# test_Project_2026-04-05_21-01-09.net
KiCad netlist of a schematic drawn in EasyEDA Pro
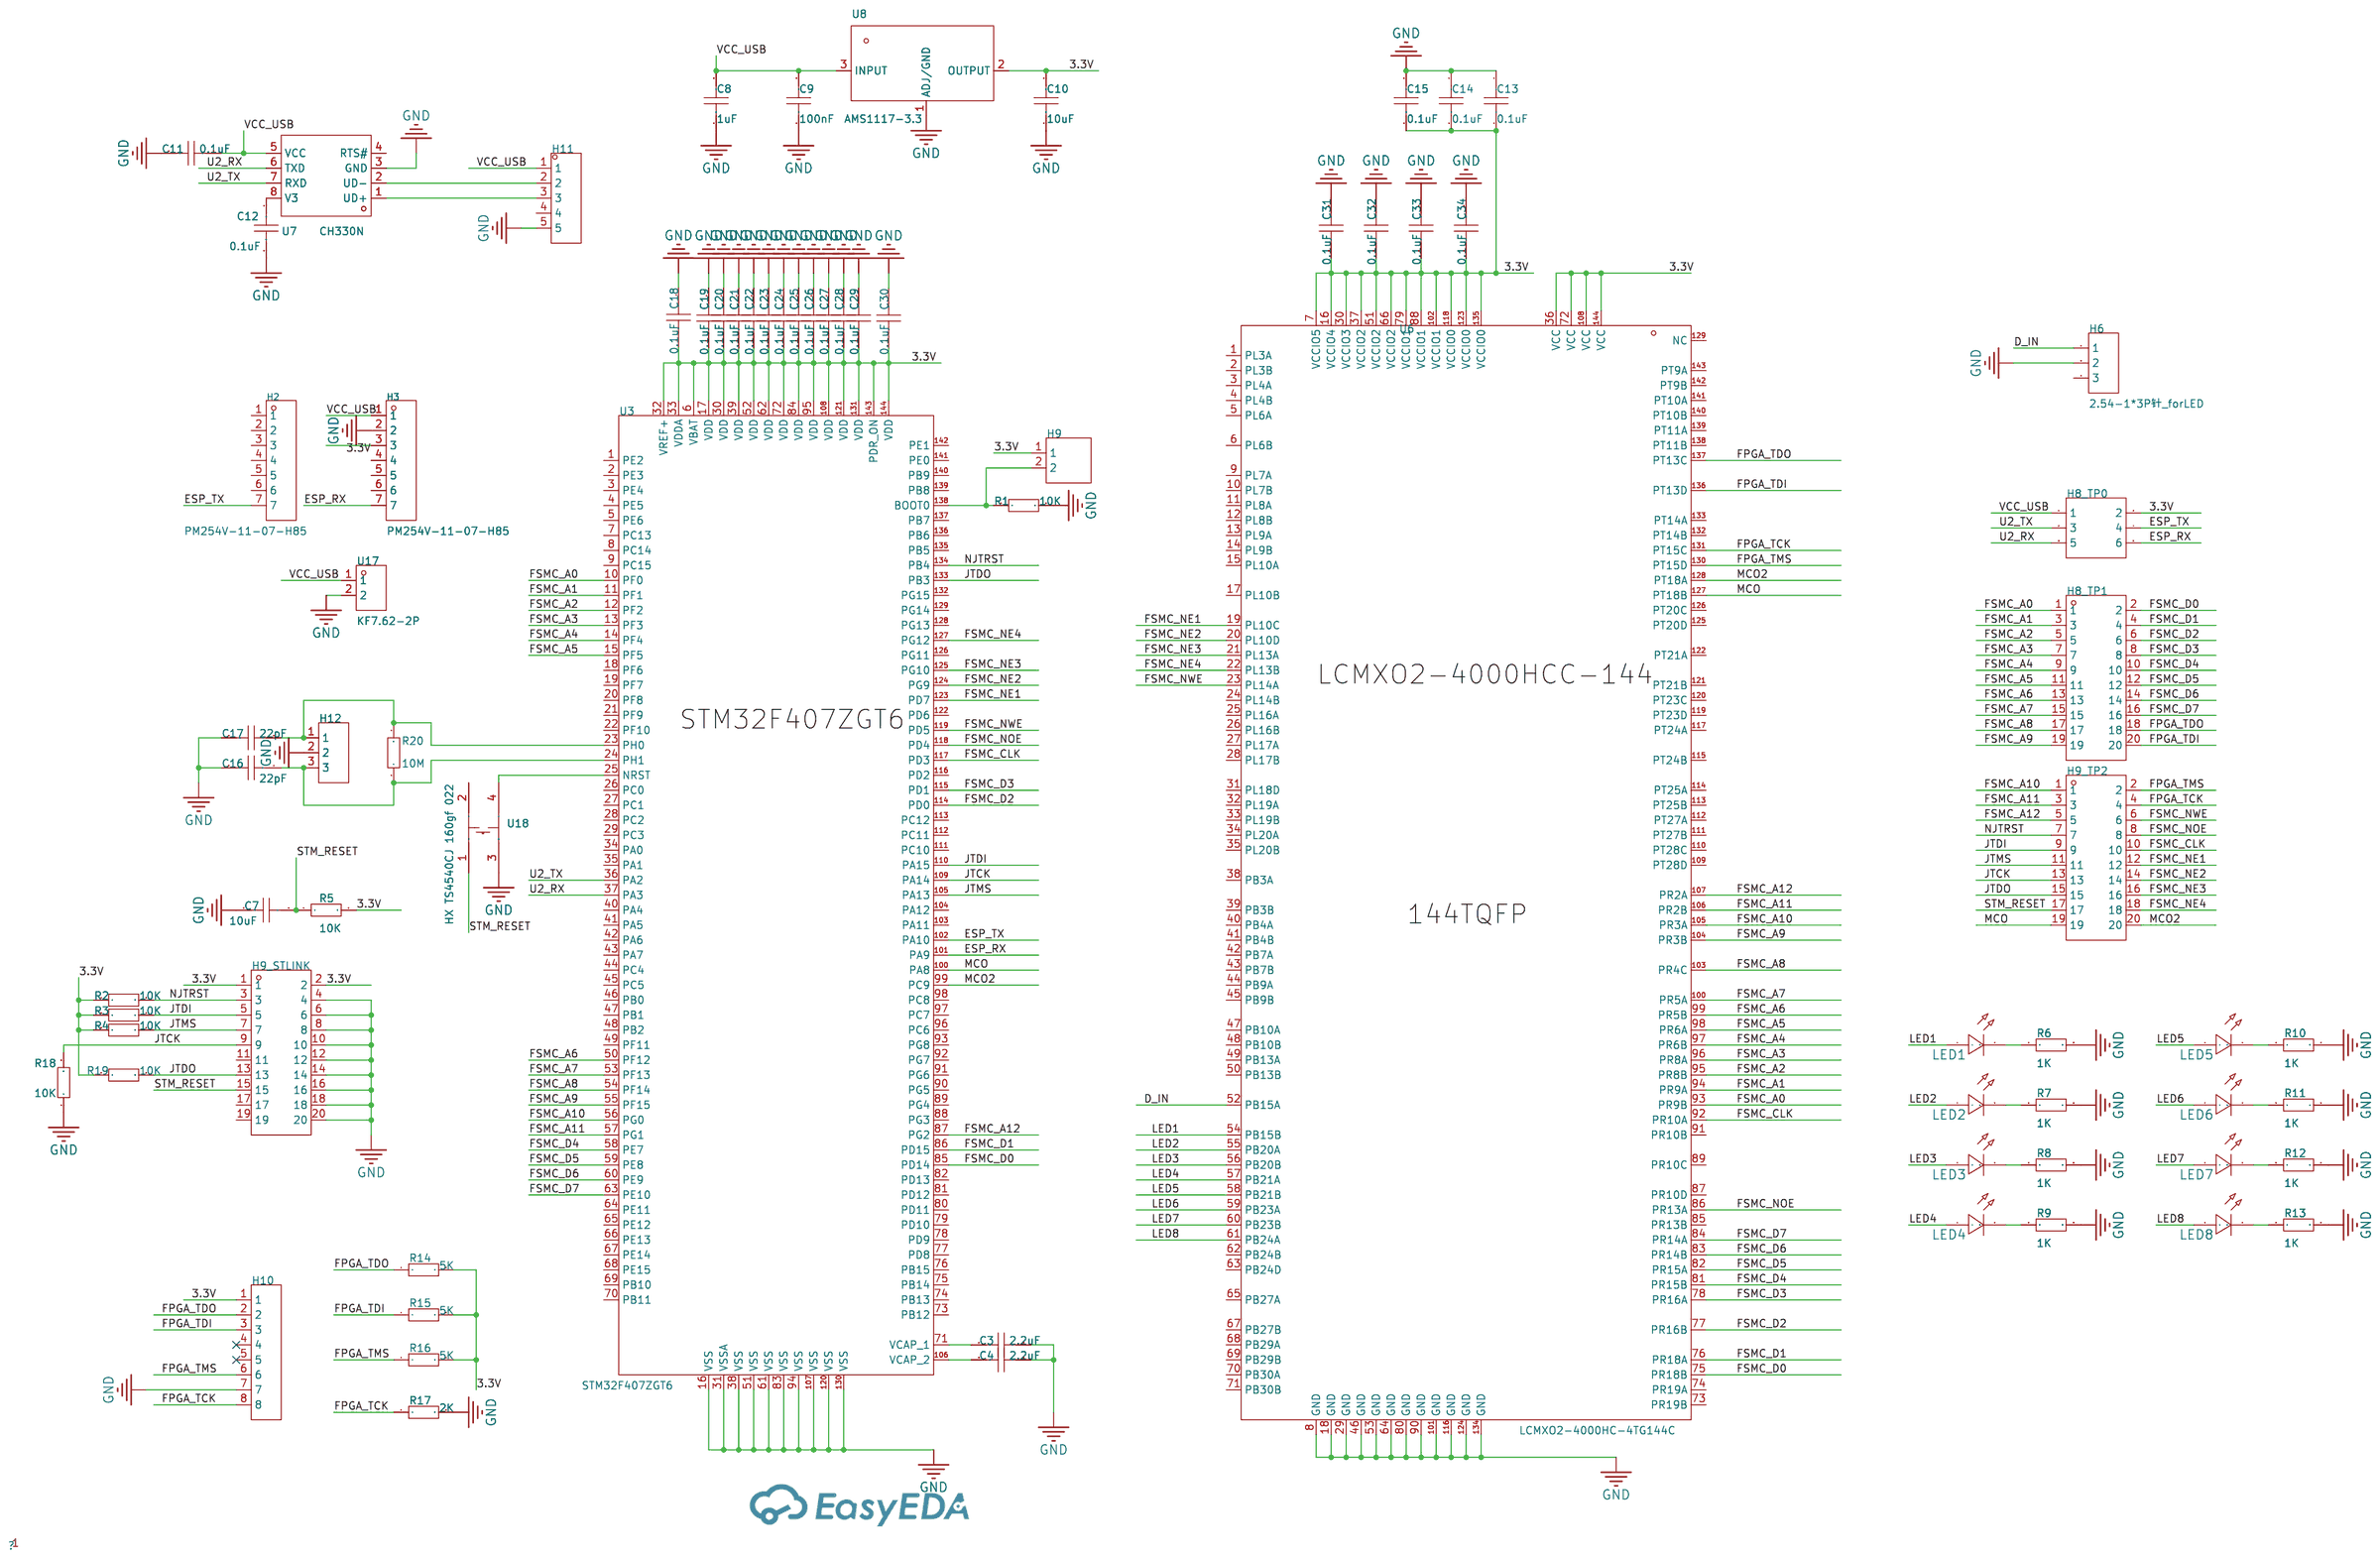
[diagram p0: schematic sheet]

(export (version "E")
  (design (tool "Eeschema 10.0.6"))
  (components
    (comp (ref "C3")
      (value "2.2uF")
      (footprint "easyedapro:C0201")
      (libsource (lib "easyedapro") (part "CAP"))
    )
    (comp (ref "C4")
      (value "2.2uF")
      (footprint "easyedapro:C0201")
      (libsource (lib "easyedapro") (part "CAP"))
    )
    (comp (ref "C7")
      (value "10uF")
      (footprint "easyedapro:C0201")
      (libsource (lib "easyedapro") (part "CAP"))
    )
    (comp (ref "C8") (value "1uF") (footprint "easyedapro:C0201") (libsource (lib "easyedapro") (part "CAP")))
    (comp (ref "C9")
      (value "100nF")
      (footprint "easyedapro:C0201")
      (libsource (lib "easyedapro") (part "CAP"))
    )
    (comp (ref "C10")
      (value "10uF")
      (footprint "easyedapro:C0201")
      (libsource (lib "easyedapro") (part "CAP"))
    )
    (comp (ref "C11")
      (value "0.1uF")
      (footprint "easyedapro:C0201")
      (libsource (lib "easyedapro") (part "CAP"))
    )
    (comp (ref "C12")
      (value "0.1uF")
      (footprint "easyedapro:C0201")
      (libsource (lib "easyedapro") (part "CAP"))
    )
    (comp (ref "C13")
      (value "0.1uF")
      (footprint "easyedapro:C0201")
      (libsource (lib "easyedapro") (part "CAP"))
    )
    (comp (ref "C14")
      (value "0.1uF")
      (footprint "easyedapro:C0201")
      (libsource (lib "easyedapro") (part "CAP"))
    )
    (comp (ref "C15")
      (value "0.1uF")
      (footprint "easyedapro:C0201")
      (libsource (lib "easyedapro") (part "CAP"))
    )
    (comp (ref "C16")
      (value "22pF")
      (footprint "easyedapro:C0201")
      (libsource (lib "easyedapro") (part "CAP"))
    )
    (comp (ref "C17")
      (value "22pF")
      (footprint "easyedapro:C0201")
      (libsource (lib "easyedapro") (part "CAP"))
    )
    (comp (ref "C18")
      (value "0.1uF")
      (footprint "easyedapro:C0201")
      (libsource (lib "easyedapro") (part "CAP"))
    )
    (comp (ref "C19")
      (value "0.1uF")
      (footprint "easyedapro:C0201")
      (libsource (lib "easyedapro") (part "CAP"))
    )
    (comp (ref "C20")
      (value "0.1uF")
      (footprint "easyedapro:C0201")
      (libsource (lib "easyedapro") (part "CAP"))
    )
    (comp (ref "C21")
      (value "0.1uF")
      (footprint "easyedapro:C0201")
      (libsource (lib "easyedapro") (part "CAP"))
    )
    (comp (ref "C22")
      (value "0.1uF")
      (footprint "easyedapro:C0201")
      (libsource (lib "easyedapro") (part "CAP"))
    )
    (comp (ref "C23")
      (value "0.1uF")
      (footprint "easyedapro:C0201")
      (libsource (lib "easyedapro") (part "CAP"))
    )
    (comp (ref "C24")
      (value "0.1uF")
      (footprint "easyedapro:C0201")
      (libsource (lib "easyedapro") (part "CAP"))
    )
    (comp (ref "C25")
      (value "0.1uF")
      (footprint "easyedapro:C0201")
      (libsource (lib "easyedapro") (part "CAP"))
    )
    (comp (ref "C26")
      (value "0.1uF")
      (footprint "easyedapro:C0201")
      (libsource (lib "easyedapro") (part "CAP"))
    )
    (comp (ref "C27")
      (value "0.1uF")
      (footprint "easyedapro:C0201")
      (libsource (lib "easyedapro") (part "CAP"))
    )
    (comp (ref "C28")
      (value "0.1uF")
      (footprint "easyedapro:C0201")
      (libsource (lib "easyedapro") (part "CAP"))
    )
    (comp (ref "C29")
      (value "0.1uF")
      (footprint "easyedapro:C0201")
      (libsource (lib "easyedapro") (part "CAP"))
    )
    (comp (ref "C30")
      (value "0.1uF")
      (footprint "easyedapro:C0201")
      (libsource (lib "easyedapro") (part "CAP"))
    )
    (comp (ref "C31")
      (value "0.1uF")
      (footprint "easyedapro:C0201")
      (libsource (lib "easyedapro") (part "CAP"))
    )
    (comp (ref "C32")
      (value "0.1uF")
      (footprint "easyedapro:C0201")
      (libsource (lib "easyedapro") (part "CAP"))
    )
    (comp (ref "C33")
      (value "0.1uF")
      (footprint "easyedapro:C0201")
      (libsource (lib "easyedapro") (part "CAP"))
    )
    (comp (ref "C34")
      (value "0.1uF")
      (footprint "easyedapro:C0201")
      (libsource (lib "easyedapro") (part "CAP"))
    )
    (comp (ref "H2")
      (value "PM254V-11-07-H85")
      (footprint "easyedapro:HDR-TH_7P-P2.54-V-F")
      (fields (field (name "Manufacturer") "XFCN(兴飞)"))
      (libsource (lib "easyedapro") (part "PM254V-11-07-H85"))
    )
    (comp (ref "H3")
      (value "PM254V-11-07-H85")
      (footprint "easyedapro:HDR-TH_7P-P2.54-V-F")
      (fields (field (name "Manufacturer") "XFCN(兴飞)"))
      (libsource (lib "easyedapro") (part "PM254V-11-07-H85"))
    )
    (comp (ref "H6")
      (value "2.54-1*3P针_forLED")
      (footprint "easyedapro:HDR-TH_3P-P2.54-V-M-1")
      (fields (field (name "Manufacturer") "BOOMELE(博穆精密)"))
      (libsource (lib "easyedapro") (part "Header-Male-2.54_1x3"))
    )
    (comp (ref "H8_TP0")
      (value "~")
      (footprint "easyedapro:HDR-TH_6P-P2.54-V-R2-C3-S2.54_A2541WV-2X3P")
      (libsource (lib "easyedapro") (part "HDR-M-2.54_2x3"))
    )
    (comp (ref "H8_TP1")
      (value "~")
      (footprint "easyedapro:HDR-TH_20P-P2.54-V-M-R2-C10-S2.54")
      (libsource (lib "easyedapro") (part "HDR-M-2.54_2x10"))
    )
    (comp (ref "H9")
      (value "~")
      (footprint "easyedapro:HDR-TH_2P-P2.54-V-M-1")
      (libsource (lib "easyedapro") (part "210S-1*2P L=11.6MMGold-plated black"))
    )
    (comp (ref "H9_STLINK")
      (value "~")
      (footprint "easyedapro:HDR-TH_20P-P2.54-V-M-R2-C10-S2.54")
      (libsource (lib "easyedapro") (part "HDR-M-2.54_2x10"))
    )
    (comp (ref "H9_TP2")
      (value "~")
      (footprint "easyedapro:HDR-TH_20P-P2.54-V-M-R2-C10-S2.54")
      (libsource (lib "easyedapro") (part "HDR-M-2.54_2x10"))
    )
    (comp (ref "H10")
      (value "~")
      (footprint "easyedapro:HDR-TH_8P-P2.54-V-F-1")
      (libsource (lib "easyedapro") (part "Header-Female-2.54_1x8"))
    )
    (comp (ref "H11")
      (value "~")
      (footprint "easyedapro:HDR-TH_5P-P2.54-V-M")
      (libsource (lib "easyedapro") (part "MTP125-1105S1"))
    )
    (comp (ref "H12")
      (value "~")
      (footprint "easyedapro:HDR-TH_3P-P2.54-V-F")
      (libsource (lib "easyedapro") (part "PM254V-11-03-H85"))
    )
    (comp (ref "LED1")
      (value "~")
      (footprint "easyedapro:LED0805-R-RD")
      (libsource (lib "easyedapro") (part "LED_R"))
    )
    (comp (ref "LED2")
      (value "~")
      (footprint "easyedapro:LED0805-R-RD")
      (libsource (lib "easyedapro") (part "LED_R"))
    )
    (comp (ref "LED3")
      (value "~")
      (footprint "easyedapro:LED0805-R-RD")
      (libsource (lib "easyedapro") (part "LED_R"))
    )
    (comp (ref "LED4")
      (value "~")
      (footprint "easyedapro:LED0805-R-RD")
      (libsource (lib "easyedapro") (part "LED_R"))
    )
    (comp (ref "LED5")
      (value "~")
      (footprint "easyedapro:LED0805-R-RD")
      (libsource (lib "easyedapro") (part "LED_R"))
    )
    (comp (ref "LED6")
      (value "~")
      (footprint "easyedapro:LED0805-R-RD")
      (libsource (lib "easyedapro") (part "LED_R"))
    )
    (comp (ref "LED7")
      (value "~")
      (footprint "easyedapro:LED0805-R-RD")
      (libsource (lib "easyedapro") (part "LED_R"))
    )
    (comp (ref "LED8")
      (value "~")
      (footprint "easyedapro:LED0805-R-RD")
      (libsource (lib "easyedapro") (part "LED_R"))
    )
    (comp (ref "R1") (value "10K") (footprint "easyedapro:R0805") (libsource (lib "easyedapro") (part "Res")))
    (comp (ref "R2") (value "10K") (footprint "easyedapro:R0805") (libsource (lib "easyedapro") (part "Res")))
    (comp (ref "R3") (value "10K") (footprint "easyedapro:R0805") (libsource (lib "easyedapro") (part "Res")))
    (comp (ref "R4") (value "10K") (footprint "easyedapro:R0805") (libsource (lib "easyedapro") (part "Res")))
    (comp (ref "R5") (value "10K") (footprint "easyedapro:R0805") (libsource (lib "easyedapro") (part "Res")))
    (comp (ref "R6") (value "1K") (footprint "easyedapro:R0805") (libsource (lib "easyedapro") (part "Res")))
    (comp (ref "R7") (value "1K") (footprint "easyedapro:R0805") (libsource (lib "easyedapro") (part "Res")))
    (comp (ref "R8") (value "1K") (footprint "easyedapro:R0805") (libsource (lib "easyedapro") (part "Res")))
    (comp (ref "R9") (value "1K") (footprint "easyedapro:R0805") (libsource (lib "easyedapro") (part "Res")))
    (comp (ref "R10") (value "1K") (footprint "easyedapro:R0805") (libsource (lib "easyedapro") (part "Res")))
    (comp (ref "R11") (value "1K") (footprint "easyedapro:R0805") (libsource (lib "easyedapro") (part "Res")))
    (comp (ref "R12") (value "1K") (footprint "easyedapro:R0805") (libsource (lib "easyedapro") (part "Res")))
    (comp (ref "R13") (value "1K") (footprint "easyedapro:R0805") (libsource (lib "easyedapro") (part "Res")))
    (comp (ref "R14") (value "5K") (footprint "easyedapro:R0805") (libsource (lib "easyedapro") (part "Res")))
    (comp (ref "R15") (value "5K") (footprint "easyedapro:R0805") (libsource (lib "easyedapro") (part "Res")))
    (comp (ref "R16") (value "5K") (footprint "easyedapro:R0805") (libsource (lib "easyedapro") (part "Res")))
    (comp (ref "R17") (value "2K") (footprint "easyedapro:R0805") (libsource (lib "easyedapro") (part "Res")))
    (comp (ref "R18")
      (value "10K")
      (footprint "easyedapro:R0805")
      (libsource (lib "easyedapro") (part "Res"))
    )
    (comp (ref "R19")
      (value "10K")
      (footprint "easyedapro:R0805")
      (libsource (lib "easyedapro") (part "Res"))
    )
    (comp (ref "R20")
      (value "10M")
      (footprint "easyedapro:R0805")
      (libsource (lib "easyedapro") (part "Res"))
    )
    (comp (ref "U3")
      (value "STM32F407ZGT6")
      (footprint "easyedapro:LQFP-144_L20.0-W20.0-P0.50-LS22.0-BL")
      (fields (field (name "Manufacturer") "ST(意法半导体)"))
      (libsource (lib "easyedapro") (part "STM32F407ZGT6"))
    )
    (comp (ref "U6")
      (value "LCMXO2-4000HC-4TG144C")
      (footprint "easyedapro:TQFP-144_L20.0-W20.0-P0.50-LS22.0-BL")
      (fields (field (name "Manufacturer") "LATTICE(莱迪思)"))
      (libsource (lib "easyedapro") (part "LCMXO2-4000HC-4TG144C"))
    )
    (comp (ref "U7")
      (value "CH330N")
      (footprint "easyedapro:SOP-8_L4.9-W3.9-P1.27-LS6.0-BL")
      (fields (field (name "Manufacturer") "WCH(南京沁恒)"))
      (libsource (lib "easyedapro") (part "CH330N"))
    )
    (comp (ref "U8")
      (value "AMS1117-3.3")
      (footprint "easyedapro:TO-252-2_L6.6-W5.6-P2.3-LS9.7")
      (fields (field (name "Manufacturer") "YONGYUTAI(永裕泰)"))
      (libsource (lib "easyedapro") (part "AMS1117-3.3_C41414107"))
    )
    (comp (ref "U17")
      (value "KF7.62-2P")
      (footprint "easyedapro:CONN-TH_KF7.62-2P")
      (fields (field (name "Manufacturer") "KEFA(科发)"))
      (libsource (lib "easyedapro") (part "KF7.62-2P"))
    )
    (comp (ref "U18")
      (value "HX TS4540CJ 160gf 022")
      (footprint "easyedapro:KEY-TH_4P-L4.5-W4.5-P3.00-LS5.0-TL")
      (fields (field (name "Manufacturer") "hanxia(韩下)"))
      (libsource (lib "easyedapro") (part "HX TS4540CJ 160GF 022"))
    )
  )
  (nets
    (net (code "1") (name "/3.3V") (class "Default")
      (node (ref "C10") (pin "1") (pinfunction "1_1") (pintype "input"))
      (node (ref "C13") (pin "2") (pinfunction "2_2") (pintype "input"))
      (node (ref "C14") (pin "2") (pinfunction "2_2") (pintype "input"))
      (node (ref "C15") (pin "2") (pinfunction "2_2") (pintype "input"))
      (node (ref "C18") (pin "2") (pinfunction "2_2") (pintype "input"))
      (node (ref "C19") (pin "2") (pinfunction "2_2") (pintype "input"))
      (node (ref "C20") (pin "2") (pinfunction "2_2") (pintype "input"))
      (node (ref "C21") (pin "2") (pinfunction "2_2") (pintype "input"))
      (node (ref "C22") (pin "2") (pinfunction "2_2") (pintype "input"))
      (node (ref "C23") (pin "2") (pinfunction "2_2") (pintype "input"))
      (node (ref "C24") (pin "2") (pinfunction "2_2") (pintype "input"))
      (node (ref "C25") (pin "2") (pinfunction "2_2") (pintype "input"))
      (node (ref "C26") (pin "2") (pinfunction "2_2") (pintype "input"))
      (node (ref "C27") (pin "2") (pinfunction "2_2") (pintype "input"))
      (node (ref "C28") (pin "2") (pinfunction "2_2") (pintype "input"))
      (node (ref "C29") (pin "2") (pinfunction "2_2") (pintype "input"))
      (node (ref "C30") (pin "2") (pinfunction "2_2") (pintype "input"))
      (node (ref "C31") (pin "2") (pinfunction "2_2") (pintype "input"))
      (node (ref "C32") (pin "2") (pinfunction "2_2") (pintype "input"))
      (node (ref "C33") (pin "2") (pinfunction "2_2") (pintype "input"))
      (node (ref "C34") (pin "2") (pinfunction "2_2") (pintype "input"))
      (node (ref "H10") (pin "1") (pinfunction "1_1") (pintype "unspecified"))
      (node (ref "H3") (pin "3") (pinfunction "3_3") (pintype "input"))
      (node (ref "H8_TP0") (pin "2") (pinfunction "2_2") (pintype "input"))
      (node (ref "H9") (pin "1") (pinfunction "1_1") (pintype "unspecified"))
      (node (ref "H9_STLINK") (pin "1") (pinfunction "1_1") (pintype "input"))
      (node (ref "H9_STLINK") (pin "2") (pinfunction "2_2") (pintype "input"))
      (node (ref "R14") (pin "2") (pinfunction "2_2") (pintype "input"))
      (node (ref "R15") (pin "2") (pinfunction "2_2") (pintype "input"))
      (node (ref "R16") (pin "2") (pinfunction "2_2") (pintype "input"))
      (node (ref "R19") (pin "1") (pinfunction "1_1") (pintype "input"))
      (node (ref "R2") (pin "1") (pinfunction "1_1") (pintype "input"))
      (node (ref "R3") (pin "1") (pinfunction "1_1") (pintype "input"))
      (node (ref "R4") (pin "1") (pinfunction "1_1") (pintype "input"))
      (node (ref "R5") (pin "2") (pinfunction "2_2") (pintype "input"))
      (node (ref "U3") (pin "108") (pinfunction "VDD_108") (pintype "unspecified"))
      (node (ref "U3") (pin "121") (pinfunction "VDD_121") (pintype "unspecified"))
      (node (ref "U3") (pin "131") (pinfunction "VDD_131") (pintype "unspecified"))
      (node (ref "U3") (pin "143") (pinfunction "PDR_ON_143") (pintype "unspecified"))
      (node (ref "U3") (pin "144") (pinfunction "VDD_144") (pintype "unspecified"))
      (node (ref "U3") (pin "17") (pinfunction "VDD_17") (pintype "unspecified"))
      (node (ref "U3") (pin "30") (pinfunction "VDD_30") (pintype "unspecified"))
      (node (ref "U3") (pin "32") (pinfunction "VREF+_32") (pintype "unspecified"))
      (node (ref "U3") (pin "33") (pinfunction "VDDA_33") (pintype "unspecified"))
      (node (ref "U3") (pin "39") (pinfunction "VDD_39") (pintype "unspecified"))
      (node (ref "U3") (pin "52") (pinfunction "VDD_52") (pintype "unspecified"))
      (node (ref "U3") (pin "6") (pinfunction "VBAT_6") (pintype "unspecified"))
      (node (ref "U3") (pin "62") (pinfunction "VDD_62") (pintype "unspecified"))
      (node (ref "U3") (pin "72") (pinfunction "VDD_72") (pintype "unspecified"))
      (node (ref "U3") (pin "84") (pinfunction "VDD_84") (pintype "unspecified"))
      (node (ref "U3") (pin "95") (pinfunction "VDD_95") (pintype "unspecified"))
      (node (ref "U6") (pin "102") (pinfunction "VCCIO1_102") (pintype "unspecified"))
      (node (ref "U6") (pin "108") (pinfunction "VCC_108") (pintype "unspecified"))
      (node (ref "U6") (pin "118") (pinfunction "VCCIO0_118") (pintype "unspecified"))
      (node (ref "U6") (pin "123") (pinfunction "VCCIO0_123") (pintype "unspecified"))
      (node (ref "U6") (pin "135") (pinfunction "VCCIO0_135") (pintype "unspecified"))
      (node (ref "U6") (pin "144") (pinfunction "VCC_144") (pintype "unspecified"))
      (node (ref "U6") (pin "16") (pinfunction "VCCIO4_16") (pintype "unspecified"))
      (node (ref "U6") (pin "30") (pinfunction "VCCIO3_30") (pintype "unspecified"))
      (node (ref "U6") (pin "36") (pinfunction "VCC_36") (pintype "unspecified"))
      (node (ref "U6") (pin "37") (pinfunction "VCCIO2_37") (pintype "unspecified"))
      (node (ref "U6") (pin "51") (pinfunction "VCCIO2_51") (pintype "unspecified"))
      (node (ref "U6") (pin "66") (pinfunction "VCCIO2_66") (pintype "unspecified"))
      (node (ref "U6") (pin "7") (pinfunction "VCCIO5_7") (pintype "unspecified"))
      (node (ref "U6") (pin "72") (pinfunction "VCC_72") (pintype "unspecified"))
      (node (ref "U6") (pin "79") (pinfunction "VCCIO1_79") (pintype "unspecified"))
      (node (ref "U6") (pin "88") (pinfunction "VCCIO1_88") (pintype "unspecified"))
      (node (ref "U8") (pin "2") (pinfunction "OUTPUT_2") (pintype "unspecified"))
    )
    (net (code "2") (name "/D_IN") (class "Default")
      (node (ref "H6") (pin "1") (pinfunction "1_1") (pintype "input"))
      (node (ref "U6") (pin "52") (pinfunction "PB15A_52") (pintype "unspecified"))
    )
    (net (code "3") (name "/ESP_RX") (class "Default")
      (node (ref "H3") (pin "7") (pinfunction "7_7") (pintype "input"))
      (node (ref "H8_TP0") (pin "6") (pinfunction "6_6") (pintype "input"))
      (node (ref "U3") (pin "101") (pinfunction "PA9_101") (pintype "unspecified"))
    )
    (net (code "4") (name "/ESP_TX") (class "Default")
      (node (ref "H2") (pin "7") (pinfunction "7_7") (pintype "input"))
      (node (ref "H8_TP0") (pin "4") (pinfunction "4_4") (pintype "input"))
      (node (ref "U3") (pin "102") (pinfunction "PA10_102") (pintype "unspecified"))
    )
    (net (code "5") (name "/FPGA_TCK") (class "Default")
      (node (ref "H10") (pin "8") (pinfunction "8_8") (pintype "unspecified"))
      (node (ref "H9_TP2") (pin "4") (pinfunction "4_4") (pintype "input"))
      (node (ref "R17") (pin "1") (pinfunction "1_1") (pintype "input"))
      (node (ref "U6") (pin "131") (pinfunction "PT15C_131") (pintype "unspecified"))
    )
    (net (code "6") (name "/FPGA_TDI") (class "Default")
      (node (ref "H10") (pin "3") (pinfunction "3_3") (pintype "unspecified"))
      (node (ref "H8_TP1") (pin "20") (pinfunction "20_20") (pintype "input"))
      (node (ref "R15") (pin "1") (pinfunction "1_1") (pintype "input"))
      (node (ref "U6") (pin "136") (pinfunction "PT13D_136") (pintype "unspecified"))
    )
    (net (code "7") (name "/FPGA_TDO") (class "Default")
      (node (ref "H10") (pin "2") (pinfunction "2_2") (pintype "unspecified"))
      (node (ref "H8_TP1") (pin "18") (pinfunction "18_18") (pintype "input"))
      (node (ref "R14") (pin "1") (pinfunction "1_1") (pintype "input"))
      (node (ref "U6") (pin "137") (pinfunction "PT13C_137") (pintype "unspecified"))
    )
    (net (code "8") (name "/FPGA_TMS") (class "Default")
      (node (ref "H10") (pin "6") (pinfunction "6_6") (pintype "unspecified"))
      (node (ref "H9_TP2") (pin "2") (pinfunction "2_2") (pintype "input"))
      (node (ref "R16") (pin "1") (pinfunction "1_1") (pintype "input"))
      (node (ref "U6") (pin "130") (pinfunction "PT15D_130") (pintype "unspecified"))
    )
    (net (code "9") (name "/FSMC_A0") (class "Default")
      (node (ref "H8_TP1") (pin "1") (pinfunction "1_1") (pintype "input"))
      (node (ref "U3") (pin "10") (pinfunction "PF0_10") (pintype "unspecified"))
      (node (ref "U6") (pin "93") (pinfunction "PR9B_93") (pintype "unspecified"))
    )
    (net (code "10") (name "/FSMC_A1") (class "Default")
      (node (ref "H8_TP1") (pin "3") (pinfunction "3_3") (pintype "input"))
      (node (ref "U3") (pin "11") (pinfunction "PF1_11") (pintype "unspecified"))
      (node (ref "U6") (pin "94") (pinfunction "PR9A_94") (pintype "unspecified"))
    )
    (net (code "11") (name "/FSMC_A2") (class "Default")
      (node (ref "H8_TP1") (pin "5") (pinfunction "5_5") (pintype "input"))
      (node (ref "U3") (pin "12") (pinfunction "PF2_12") (pintype "unspecified"))
      (node (ref "U6") (pin "95") (pinfunction "PR8B_95") (pintype "unspecified"))
    )
    (net (code "12") (name "/FSMC_A3") (class "Default")
      (node (ref "H8_TP1") (pin "7") (pinfunction "7_7") (pintype "input"))
      (node (ref "U3") (pin "13") (pinfunction "PF3_13") (pintype "unspecified"))
      (node (ref "U6") (pin "96") (pinfunction "PR8A_96") (pintype "unspecified"))
    )
    (net (code "13") (name "/FSMC_A4") (class "Default")
      (node (ref "H8_TP1") (pin "9") (pinfunction "9_9") (pintype "input"))
      (node (ref "U3") (pin "14") (pinfunction "PF4_14") (pintype "unspecified"))
      (node (ref "U6") (pin "97") (pinfunction "PR6B_97") (pintype "unspecified"))
    )
    (net (code "14") (name "/FSMC_A5") (class "Default")
      (node (ref "H8_TP1") (pin "11") (pinfunction "11_11") (pintype "input"))
      (node (ref "U3") (pin "15") (pinfunction "PF5_15") (pintype "unspecified"))
      (node (ref "U6") (pin "98") (pinfunction "PR6A_98") (pintype "unspecified"))
    )
    (net (code "15") (name "/FSMC_A6") (class "Default")
      (node (ref "H8_TP1") (pin "13") (pinfunction "13_13") (pintype "input"))
      (node (ref "U3") (pin "50") (pinfunction "PF12_50") (pintype "unspecified"))
      (node (ref "U6") (pin "99") (pinfunction "PR5B_99") (pintype "unspecified"))
    )
    (net (code "16") (name "/FSMC_A7") (class "Default")
      (node (ref "H8_TP1") (pin "15") (pinfunction "15_15") (pintype "input"))
      (node (ref "U3") (pin "53") (pinfunction "PF13_53") (pintype "unspecified"))
      (node (ref "U6") (pin "100") (pinfunction "PR5A_100") (pintype "unspecified"))
    )
    (net (code "17") (name "/FSMC_A8") (class "Default")
      (node (ref "H8_TP1") (pin "17") (pinfunction "17_17") (pintype "input"))
      (node (ref "U3") (pin "54") (pinfunction "PF14_54") (pintype "unspecified"))
      (node (ref "U6") (pin "103") (pinfunction "PR4C_103") (pintype "unspecified"))
    )
    (net (code "18") (name "/FSMC_A9") (class "Default")
      (node (ref "H8_TP1") (pin "19") (pinfunction "19_19") (pintype "input"))
      (node (ref "U3") (pin "55") (pinfunction "PF15_55") (pintype "unspecified"))
      (node (ref "U6") (pin "104") (pinfunction "PR3B_104") (pintype "unspecified"))
    )
    (net (code "19") (name "/FSMC_A10") (class "Default")
      (node (ref "H9_TP2") (pin "1") (pinfunction "1_1") (pintype "input"))
      (node (ref "U3") (pin "56") (pinfunction "PG0_56") (pintype "unspecified"))
      (node (ref "U6") (pin "105") (pinfunction "PR3A_105") (pintype "unspecified"))
    )
    (net (code "20") (name "/FSMC_A11") (class "Default")
      (node (ref "H9_TP2") (pin "3") (pinfunction "3_3") (pintype "input"))
      (node (ref "U3") (pin "57") (pinfunction "PG1_57") (pintype "unspecified"))
      (node (ref "U6") (pin "106") (pinfunction "PR2B_106") (pintype "unspecified"))
    )
    (net (code "21") (name "/FSMC_A12") (class "Default")
      (node (ref "H9_TP2") (pin "5") (pinfunction "5_5") (pintype "input"))
      (node (ref "U3") (pin "87") (pinfunction "PG2_87") (pintype "unspecified"))
      (node (ref "U6") (pin "107") (pinfunction "PR2A_107") (pintype "unspecified"))
    )
    (net (code "22") (name "/FSMC_CLK") (class "Default")
      (node (ref "H9_TP2") (pin "10") (pinfunction "10_10") (pintype "input"))
      (node (ref "U3") (pin "117") (pinfunction "PD3_117") (pintype "unspecified"))
      (node (ref "U6") (pin "92") (pinfunction "PR10A_92") (pintype "unspecified"))
    )
    (net (code "23") (name "/FSMC_D0") (class "Default")
      (node (ref "H8_TP1") (pin "2") (pinfunction "2_2") (pintype "input"))
      (node (ref "U3") (pin "85") (pinfunction "PD14_85") (pintype "unspecified"))
      (node (ref "U6") (pin "75") (pinfunction "PR18B_75") (pintype "unspecified"))
    )
    (net (code "24") (name "/FSMC_D1") (class "Default")
      (node (ref "H8_TP1") (pin "4") (pinfunction "4_4") (pintype "input"))
      (node (ref "U3") (pin "86") (pinfunction "PD15_86") (pintype "unspecified"))
      (node (ref "U6") (pin "76") (pinfunction "PR18A_76") (pintype "unspecified"))
    )
    (net (code "25") (name "/FSMC_D2") (class "Default")
      (node (ref "H8_TP1") (pin "6") (pinfunction "6_6") (pintype "input"))
      (node (ref "U3") (pin "114") (pinfunction "PD0_114") (pintype "unspecified"))
      (node (ref "U6") (pin "77") (pinfunction "PR16B_77") (pintype "unspecified"))
    )
    (net (code "26") (name "/FSMC_D3") (class "Default")
      (node (ref "H8_TP1") (pin "8") (pinfunction "8_8") (pintype "input"))
      (node (ref "U3") (pin "115") (pinfunction "PD1_115") (pintype "unspecified"))
      (node (ref "U6") (pin "78") (pinfunction "PR16A_78") (pintype "unspecified"))
    )
    (net (code "27") (name "/FSMC_D4") (class "Default")
      (node (ref "H8_TP1") (pin "10") (pinfunction "10_10") (pintype "input"))
      (node (ref "U3") (pin "58") (pinfunction "PE7_58") (pintype "unspecified"))
      (node (ref "U6") (pin "81") (pinfunction "PR15B_81") (pintype "unspecified"))
    )
    (net (code "28") (name "/FSMC_D5") (class "Default")
      (node (ref "H8_TP1") (pin "12") (pinfunction "12_12") (pintype "input"))
      (node (ref "U3") (pin "59") (pinfunction "PE8_59") (pintype "unspecified"))
      (node (ref "U6") (pin "82") (pinfunction "PR15A_82") (pintype "unspecified"))
    )
    (net (code "29") (name "/FSMC_D6") (class "Default")
      (node (ref "H8_TP1") (pin "14") (pinfunction "14_14") (pintype "input"))
      (node (ref "U3") (pin "60") (pinfunction "PE9_60") (pintype "unspecified"))
      (node (ref "U6") (pin "83") (pinfunction "PR14B_83") (pintype "unspecified"))
    )
    (net (code "30") (name "/FSMC_D7") (class "Default")
      (node (ref "H8_TP1") (pin "16") (pinfunction "16_16") (pintype "input"))
      (node (ref "U3") (pin "63") (pinfunction "PE10_63") (pintype "unspecified"))
      (node (ref "U6") (pin "84") (pinfunction "PR14A_84") (pintype "unspecified"))
    )
    (net (code "31") (name "/FSMC_NE1") (class "Default")
      (node (ref "H9_TP2") (pin "12") (pinfunction "12_12") (pintype "input"))
      (node (ref "U3") (pin "123") (pinfunction "PD7_123") (pintype "unspecified"))
      (node (ref "U6") (pin "19") (pinfunction "PL10C_19") (pintype "unspecified"))
    )
    (net (code "32") (name "/FSMC_NE2") (class "Default")
      (node (ref "H9_TP2") (pin "14") (pinfunction "14_14") (pintype "input"))
      (node (ref "U3") (pin "124") (pinfunction "PG9_124") (pintype "unspecified"))
      (node (ref "U6") (pin "20") (pinfunction "PL10D_20") (pintype "unspecified"))
    )
    (net (code "33") (name "/FSMC_NE3") (class "Default")
      (node (ref "H9_TP2") (pin "16") (pinfunction "16_16") (pintype "input"))
      (node (ref "U3") (pin "125") (pinfunction "PG10_125") (pintype "unspecified"))
      (node (ref "U6") (pin "21") (pinfunction "PL13A_21") (pintype "unspecified"))
    )
    (net (code "34") (name "/FSMC_NE4") (class "Default")
      (node (ref "H9_TP2") (pin "18") (pinfunction "18_18") (pintype "input"))
      (node (ref "U3") (pin "127") (pinfunction "PG12_127") (pintype "unspecified"))
      (node (ref "U6") (pin "22") (pinfunction "PL13B_22") (pintype "unspecified"))
    )
    (net (code "35") (name "/FSMC_NOE") (class "Default")
      (node (ref "H9_TP2") (pin "8") (pinfunction "8_8") (pintype "input"))
      (node (ref "U3") (pin "118") (pinfunction "PD4_118") (pintype "unspecified"))
      (node (ref "U6") (pin "86") (pinfunction "PR13A_86") (pintype "unspecified"))
    )
    (net (code "36") (name "/FSMC_NWE") (class "Default")
      (node (ref "H9_TP2") (pin "6") (pinfunction "6_6") (pintype "input"))
      (node (ref "U3") (pin "119") (pinfunction "PD5_119") (pintype "unspecified"))
      (node (ref "U6") (pin "23") (pinfunction "PL14A_23") (pintype "unspecified"))
    )
    (net (code "37") (name "/JTCK") (class "Default")
      (node (ref "H9_STLINK") (pin "9") (pinfunction "9_9") (pintype "input"))
      (node (ref "H9_TP2") (pin "13") (pinfunction "13_13") (pintype "input"))
      (node (ref "R18") (pin "2") (pinfunction "2_2") (pintype "input"))
      (node (ref "U3") (pin "109") (pinfunction "PA14_109") (pintype "unspecified"))
    )
    (net (code "38") (name "/JTDI") (class "Default")
      (node (ref "H9_STLINK") (pin "5") (pinfunction "5_5") (pintype "input"))
      (node (ref "H9_TP2") (pin "9") (pinfunction "9_9") (pintype "input"))
      (node (ref "R3") (pin "2") (pinfunction "2_2") (pintype "input"))
      (node (ref "U3") (pin "110") (pinfunction "PA15_110") (pintype "unspecified"))
    )
    (net (code "39") (name "/JTDO") (class "Default")
      (node (ref "H9_STLINK") (pin "13") (pinfunction "13_13") (pintype "input"))
      (node (ref "H9_TP2") (pin "15") (pinfunction "15_15") (pintype "input"))
      (node (ref "R19") (pin "2") (pinfunction "2_2") (pintype "input"))
      (node (ref "U3") (pin "133") (pinfunction "PB3_133") (pintype "unspecified"))
    )
    (net (code "40") (name "/JTMS") (class "Default")
      (node (ref "H9_STLINK") (pin "7") (pinfunction "7_7") (pintype "input"))
      (node (ref "H9_TP2") (pin "11") (pinfunction "11_11") (pintype "input"))
      (node (ref "R4") (pin "2") (pinfunction "2_2") (pintype "input"))
      (node (ref "U3") (pin "105") (pinfunction "PA13_105") (pintype "unspecified"))
    )
    (net (code "41") (name "/LED1") (class "Default")
      (node (ref "LED1") (pin "1") (pinfunction "A_1") (pintype "input"))
      (node (ref "U6") (pin "54") (pinfunction "PB15B_54") (pintype "unspecified"))
    )
    (net (code "42") (name "/LED2") (class "Default")
      (node (ref "LED2") (pin "1") (pinfunction "A_1") (pintype "input"))
      (node (ref "U6") (pin "55") (pinfunction "PB20A_55") (pintype "unspecified"))
    )
    (net (code "43") (name "/LED3") (class "Default")
      (node (ref "LED3") (pin "1") (pinfunction "A_1") (pintype "input"))
      (node (ref "U6") (pin "56") (pinfunction "PB20B_56") (pintype "unspecified"))
    )
    (net (code "44") (name "/LED4") (class "Default")
      (node (ref "LED4") (pin "1") (pinfunction "A_1") (pintype "input"))
      (node (ref "U6") (pin "57") (pinfunction "PB21A_57") (pintype "unspecified"))
    )
    (net (code "45") (name "/LED5") (class "Default")
      (node (ref "LED5") (pin "1") (pinfunction "A_1") (pintype "input"))
      (node (ref "U6") (pin "58") (pinfunction "PB21B_58") (pintype "unspecified"))
    )
    (net (code "46") (name "/LED6") (class "Default")
      (node (ref "LED6") (pin "1") (pinfunction "A_1") (pintype "input"))
      (node (ref "U6") (pin "59") (pinfunction "PB23A_59") (pintype "unspecified"))
    )
    (net (code "47") (name "/LED7") (class "Default")
      (node (ref "LED7") (pin "1") (pinfunction "A_1") (pintype "input"))
      (node (ref "U6") (pin "60") (pinfunction "PB23B_60") (pintype "unspecified"))
    )
    (net (code "48") (name "/LED8") (class "Default")
      (node (ref "LED8") (pin "1") (pinfunction "A_1") (pintype "input"))
      (node (ref "U6") (pin "61") (pinfunction "PB24A_61") (pintype "unspecified"))
    )
    (net (code "49") (name "/MCO") (class "Default")
      (node (ref "H9_TP2") (pin "19") (pinfunction "19_19") (pintype "input"))
      (node (ref "U3") (pin "100") (pinfunction "PA8_100") (pintype "unspecified"))
      (node (ref "U6") (pin "127") (pinfunction "PT18B_127") (pintype "unspecified"))
    )
    (net (code "50") (name "/MCO2") (class "Default")
      (node (ref "H9_TP2") (pin "20") (pinfunction "20_20") (pintype "input"))
      (node (ref "U3") (pin "99") (pinfunction "PC9_99") (pintype "unspecified"))
      (node (ref "U6") (pin "128") (pinfunction "PT18A_128") (pintype "unspecified"))
    )
    (net (code "51") (name "/NJTRST") (class "Default")
      (node (ref "H9_STLINK") (pin "3") (pinfunction "3_3") (pintype "input"))
      (node (ref "H9_TP2") (pin "7") (pinfunction "7_7") (pintype "input"))
      (node (ref "R2") (pin "2") (pinfunction "2_2") (pintype "input"))
      (node (ref "U3") (pin "134") (pinfunction "PB4_134") (pintype "unspecified"))
    )
    (net (code "52") (name "/STM_RESET") (class "Default")
      (node (ref "C7") (pin "1") (pinfunction "1_1") (pintype "input"))
      (node (ref "H9_STLINK") (pin "15") (pinfunction "15_15") (pintype "input"))
      (node (ref "H9_TP2") (pin "17") (pinfunction "17_17") (pintype "input"))
      (node (ref "R5") (pin "1") (pinfunction "1_1") (pintype "input"))
      (node (ref "U18") (pin "1") (pinfunction "1_1") (pintype "unspecified"))
    )
    (net (code "53") (name "/U2_RX") (class "Default")
      (node (ref "H8_TP0") (pin "5") (pinfunction "5_5") (pintype "input"))
      (node (ref "U3") (pin "37") (pinfunction "PA3_37") (pintype "unspecified"))
      (node (ref "U7") (pin "6") (pinfunction "TXD_6") (pintype "unspecified"))
    )
    (net (code "54") (name "/U2_TX") (class "Default")
      (node (ref "H8_TP0") (pin "3") (pinfunction "3_3") (pintype "input"))
      (node (ref "U3") (pin "36") (pinfunction "PA2_36") (pintype "unspecified"))
      (node (ref "U7") (pin "7") (pinfunction "RXD_7") (pintype "unspecified"))
    )
    (net (code "55") (name "/VCC_USB") (class "Default")
      (node (ref "C11") (pin "1") (pinfunction "1_1") (pintype "input"))
      (node (ref "C8") (pin "1") (pinfunction "1_1") (pintype "input"))
      (node (ref "C9") (pin "1") (pinfunction "1_1") (pintype "input"))
      (node (ref "H11") (pin "1") (pinfunction "1_1") (pintype "input"))
      (node (ref "H3") (pin "1") (pinfunction "1_1") (pintype "input"))
      (node (ref "H8_TP0") (pin "1") (pinfunction "1_1") (pintype "input"))
      (node (ref "U17") (pin "1") (pinfunction "1_1") (pintype "unspecified"))
      (node (ref "U7") (pin "5") (pinfunction "VCC_5") (pintype "unspecified"))
      (node (ref "U8") (pin "3") (pinfunction "INPUT_3") (pintype "unspecified"))
    )
    (net (code "56") (name "GND") (class "Default")
      (node (ref "C10") (pin "2") (pinfunction "2_2") (pintype "input"))
      (node (ref "C11") (pin "2") (pinfunction "2_2") (pintype "input"))
      (node (ref "C12") (pin "2") (pinfunction "2_2") (pintype "input"))
      (node (ref "C13") (pin "1") (pinfunction "1_1") (pintype "input"))
      (node (ref "C14") (pin "1") (pinfunction "1_1") (pintype "input"))
      (node (ref "C15") (pin "1") (pinfunction "1_1") (pintype "input"))
      (node (ref "C16") (pin "2") (pinfunction "2_2") (pintype "input"))
      (node (ref "C17") (pin "2") (pinfunction "2_2") (pintype "input"))
      (node (ref "C18") (pin "1") (pinfunction "1_1") (pintype "input"))
      (node (ref "C19") (pin "1") (pinfunction "1_1") (pintype "input"))
      (node (ref "C20") (pin "1") (pinfunction "1_1") (pintype "input"))
      (node (ref "C21") (pin "1") (pinfunction "1_1") (pintype "input"))
      (node (ref "C22") (pin "1") (pinfunction "1_1") (pintype "input"))
      (node (ref "C23") (pin "1") (pinfunction "1_1") (pintype "input"))
      (node (ref "C24") (pin "1") (pinfunction "1_1") (pintype "input"))
      (node (ref "C25") (pin "1") (pinfunction "1_1") (pintype "input"))
      (node (ref "C26") (pin "1") (pinfunction "1_1") (pintype "input"))
      (node (ref "C27") (pin "1") (pinfunction "1_1") (pintype "input"))
      (node (ref "C28") (pin "1") (pinfunction "1_1") (pintype "input"))
      (node (ref "C29") (pin "1") (pinfunction "1_1") (pintype "input"))
      (node (ref "C3") (pin "1") (pinfunction "1_1") (pintype "input"))
      (node (ref "C30") (pin "1") (pinfunction "1_1") (pintype "input"))
      (node (ref "C31") (pin "1") (pinfunction "1_1") (pintype "input"))
      (node (ref "C32") (pin "1") (pinfunction "1_1") (pintype "input"))
      (node (ref "C33") (pin "1") (pinfunction "1_1") (pintype "input"))
      (node (ref "C34") (pin "1") (pinfunction "1_1") (pintype "input"))
      (node (ref "C4") (pin "1") (pinfunction "1_1") (pintype "input"))
      (node (ref "C7") (pin "2") (pinfunction "2_2") (pintype "input"))
      (node (ref "C8") (pin "2") (pinfunction "2_2") (pintype "input"))
      (node (ref "C9") (pin "2") (pinfunction "2_2") (pintype "input"))
      (node (ref "H10") (pin "7") (pinfunction "7_7") (pintype "unspecified"))
      (node (ref "H11") (pin "5") (pinfunction "5_5") (pintype "input"))
      (node (ref "H12") (pin "2") (pinfunction "2_2") (pintype "unspecified"))
      (node (ref "H3") (pin "2") (pinfunction "2_2") (pintype "input"))
      (node (ref "H6") (pin "2") (pinfunction "2_2") (pintype "input"))
      (node (ref "H9_STLINK") (pin "10") (pinfunction "10_10") (pintype "input"))
      (node (ref "H9_STLINK") (pin "12") (pinfunction "12_12") (pintype "input"))
      (node (ref "H9_STLINK") (pin "14") (pinfunction "14_14") (pintype "input"))
      (node (ref "H9_STLINK") (pin "16") (pinfunction "16_16") (pintype "input"))
      (node (ref "H9_STLINK") (pin "18") (pinfunction "18_18") (pintype "input"))
      (node (ref "H9_STLINK") (pin "20") (pinfunction "20_20") (pintype "input"))
      (node (ref "H9_STLINK") (pin "4") (pinfunction "4_4") (pintype "input"))
      (node (ref "H9_STLINK") (pin "6") (pinfunction "6_6") (pintype "input"))
      (node (ref "H9_STLINK") (pin "8") (pinfunction "8_8") (pintype "input"))
      (node (ref "R1") (pin "2") (pinfunction "2_2") (pintype "input"))
      (node (ref "R10") (pin "2") (pinfunction "2_2") (pintype "input"))
      (node (ref "R11") (pin "2") (pinfunction "2_2") (pintype "input"))
      (node (ref "R12") (pin "2") (pinfunction "2_2") (pintype "input"))
      (node (ref "R13") (pin "2") (pinfunction "2_2") (pintype "input"))
      (node (ref "R17") (pin "2") (pinfunction "2_2") (pintype "input"))
      (node (ref "R18") (pin "1") (pinfunction "1_1") (pintype "input"))
      (node (ref "R6") (pin "2") (pinfunction "2_2") (pintype "input"))
      (node (ref "R7") (pin "2") (pinfunction "2_2") (pintype "input"))
      (node (ref "R8") (pin "2") (pinfunction "2_2") (pintype "input"))
      (node (ref "R9") (pin "2") (pinfunction "2_2") (pintype "input"))
      (node (ref "U17") (pin "2") (pinfunction "2_2") (pintype "unspecified"))
      (node (ref "U18") (pin "3") (pinfunction "3_3") (pintype "unspecified"))
      (node (ref "U3") (pin "107") (pinfunction "VSS_107") (pintype "unspecified"))
      (node (ref "U3") (pin "120") (pinfunction "VSS_120") (pintype "unspecified"))
      (node (ref "U3") (pin "130") (pinfunction "VSS_130") (pintype "unspecified"))
      (node (ref "U3") (pin "16") (pinfunction "VSS_16") (pintype "unspecified"))
      (node (ref "U3") (pin "31") (pinfunction "VSSA_31") (pintype "unspecified"))
      (node (ref "U3") (pin "38") (pinfunction "VSS_38") (pintype "unspecified"))
      (node (ref "U3") (pin "51") (pinfunction "VSS_51") (pintype "unspecified"))
      (node (ref "U3") (pin "61") (pinfunction "VSS_61") (pintype "unspecified"))
      (node (ref "U3") (pin "83") (pinfunction "VSS_83") (pintype "unspecified"))
      (node (ref "U3") (pin "94") (pinfunction "VSS_94") (pintype "unspecified"))
      (node (ref "U6") (pin "101") (pinfunction "GND_101") (pintype "unspecified"))
      (node (ref "U6") (pin "116") (pinfunction "GND_116") (pintype "unspecified"))
      (node (ref "U6") (pin "124") (pinfunction "GND_124") (pintype "unspecified"))
      (node (ref "U6") (pin "134") (pinfunction "GND_134") (pintype "unspecified"))
      (node (ref "U6") (pin "18") (pinfunction "GND_18") (pintype "unspecified"))
      (node (ref "U6") (pin "29") (pinfunction "GND_29") (pintype "unspecified"))
      (node (ref "U6") (pin "46") (pinfunction "GND_46") (pintype "unspecified"))
      (node (ref "U6") (pin "53") (pinfunction "GND_53") (pintype "unspecified"))
      (node (ref "U6") (pin "64") (pinfunction "GND_64") (pintype "unspecified"))
      (node (ref "U6") (pin "8") (pinfunction "GND_8") (pintype "unspecified"))
      (node (ref "U6") (pin "80") (pinfunction "GND_80") (pintype "unspecified"))
      (node (ref "U6") (pin "90") (pinfunction "GND_90") (pintype "unspecified"))
      (node (ref "U7") (pin "3") (pinfunction "GND_3") (pintype "unspecified"))
      (node (ref "U8") (pin "1") (pinfunction "ADJ/GND_1") (pintype "unspecified"))
    )
    (net (code "57") (name "Net-(LED1-C)") (class "Default")
      (node (ref "LED1") (pin "2") (pinfunction "C_2") (pintype "input"))
      (node (ref "R6") (pin "1") (pinfunction "1_1") (pintype "input"))
    )
    (net (code "58") (name "Net-(LED2-C)") (class "Default")
      (node (ref "LED2") (pin "2") (pinfunction "C_2") (pintype "input"))
      (node (ref "R7") (pin "1") (pinfunction "1_1") (pintype "input"))
    )
    (net (code "59") (name "Net-(LED3-C)") (class "Default")
      (node (ref "LED3") (pin "2") (pinfunction "C_2") (pintype "input"))
      (node (ref "R8") (pin "1") (pinfunction "1_1") (pintype "input"))
    )
    (net (code "60") (name "Net-(LED4-C)") (class "Default")
      (node (ref "LED4") (pin "2") (pinfunction "C_2") (pintype "input"))
      (node (ref "R9") (pin "1") (pinfunction "1_1") (pintype "input"))
    )
    (net (code "61") (name "Net-(LED5-C)") (class "Default")
      (node (ref "LED5") (pin "2") (pinfunction "C_2") (pintype "input"))
      (node (ref "R10") (pin "1") (pinfunction "1_1") (pintype "input"))
    )
    (net (code "62") (name "Net-(LED6-C)") (class "Default")
      (node (ref "LED6") (pin "2") (pinfunction "C_2") (pintype "input"))
      (node (ref "R11") (pin "1") (pinfunction "1_1") (pintype "input"))
    )
    (net (code "63") (name "Net-(LED7-C)") (class "Default")
      (node (ref "LED7") (pin "2") (pinfunction "C_2") (pintype "input"))
      (node (ref "R12") (pin "1") (pinfunction "1_1") (pintype "input"))
    )
    (net (code "64") (name "Net-(LED8-C)") (class "Default")
      (node (ref "LED8") (pin "2") (pinfunction "C_2") (pintype "input"))
      (node (ref "R13") (pin "1") (pinfunction "1_1") (pintype "input"))
    )
    (net (code "65") (name "Net-(U3-BOOT0)") (class "Default")
      (node (ref "H9") (pin "2") (pinfunction "2_2") (pintype "unspecified"))
      (node (ref "R1") (pin "1") (pinfunction "1_1") (pintype "input"))
      (node (ref "U3") (pin "138") (pinfunction "BOOT0_138") (pintype "unspecified"))
    )
    (net (code "66") (name "Net-(U3-NRST)") (class "Default")
      (node (ref "U18") (pin "4") (pinfunction "4_4") (pintype "unspecified"))
      (node (ref "U3") (pin "25") (pinfunction "NRST_25") (pintype "unspecified"))
    )
    (net (code "67") (name "Net-(U3-PH0)") (class "Default")
      (node (ref "C17") (pin "1") (pinfunction "1_1") (pintype "input"))
      (node (ref "H12") (pin "1") (pinfunction "1_1") (pintype "unspecified"))
      (node (ref "R20") (pin "2") (pinfunction "2_2") (pintype "input"))
      (node (ref "U3") (pin "23") (pinfunction "PH0_23") (pintype "unspecified"))
    )
    (net (code "68") (name "Net-(U3-PH1)") (class "Default")
      (node (ref "C16") (pin "1") (pinfunction "1_1") (pintype "input"))
      (node (ref "H12") (pin "3") (pinfunction "3_3") (pintype "unspecified"))
      (node (ref "R20") (pin "1") (pinfunction "1_1") (pintype "input"))
      (node (ref "U3") (pin "24") (pinfunction "PH1_24") (pintype "unspecified"))
    )
    (net (code "69") (name "Net-(U3-VCAP_1)") (class "Default")
      (node (ref "C3") (pin "2") (pinfunction "2_2") (pintype "input"))
      (node (ref "U3") (pin "71") (pinfunction "VCAP_1_71") (pintype "unspecified"))
    )
    (net (code "70") (name "Net-(U3-VCAP_2)") (class "Default")
      (node (ref "C4") (pin "2") (pinfunction "2_2") (pintype "input"))
      (node (ref "U3") (pin "106") (pinfunction "VCAP_2_106") (pintype "unspecified"))
    )
    (net (code "71") (name "Net-(U7-UD+)") (class "Default")
      (node (ref "H11") (pin "3") (pinfunction "3_3") (pintype "input"))
      (node (ref "U7") (pin "1") (pinfunction "UD+_1") (pintype "unspecified"))
    )
    (net (code "72") (name "Net-(U7-UD-)") (class "Default")
      (node (ref "H11") (pin "2") (pinfunction "2_2") (pintype "input"))
      (node (ref "U7") (pin "2") (pinfunction "UD-_2") (pintype "unspecified"))
    )
    (net (code "73") (name "Net-(U7-V3)") (class "Default")
      (node (ref "C12") (pin "1") (pinfunction "1_1") (pintype "input"))
      (node (ref "U7") (pin "8") (pinfunction "V3_8") (pintype "unspecified"))
    )
    (net (code "74") (name "unconnected-(H2-Pad1)") (class "Default")
      (node (ref "H2") (pin "1") (pinfunction "1_1") (pintype "input"))
    )
    (net (code "75") (name "unconnected-(H2-Pad2)") (class "Default")
      (node (ref "H2") (pin "2") (pinfunction "2_2") (pintype "input"))
    )
    (net (code "76") (name "unconnected-(H2-Pad3)") (class "Default")
      (node (ref "H2") (pin "3") (pinfunction "3_3") (pintype "input"))
    )
    (net (code "77") (name "unconnected-(H2-Pad4)") (class "Default")
      (node (ref "H2") (pin "4") (pinfunction "4_4") (pintype "input"))
    )
    (net (code "78") (name "unconnected-(H2-Pad5)") (class "Default")
      (node (ref "H2") (pin "5") (pinfunction "5_5") (pintype "input"))
    )
    (net (code "79") (name "unconnected-(H2-Pad6)") (class "Default")
      (node (ref "H2") (pin "6") (pinfunction "6_6") (pintype "input"))
    )
    (net (code "80") (name "unconnected-(H3-Pad4)") (class "Default")
      (node (ref "H3") (pin "4") (pinfunction "4_4") (pintype "input"))
    )
    (net (code "81") (name "unconnected-(H3-Pad5)") (class "Default")
      (node (ref "H3") (pin "5") (pinfunction "5_5") (pintype "input"))
    )
    (net (code "82") (name "unconnected-(H3-Pad6)") (class "Default")
      (node (ref "H3") (pin "6") (pinfunction "6_6") (pintype "input"))
    )
    (net (code "83") (name "unconnected-(H6-Pad3)") (class "Default")
      (node (ref "H6") (pin "3") (pinfunction "3_3") (pintype "input"))
    )
    (net (code "84") (name "unconnected-(H9_STLINK-Pad11)") (class "Default")
      (node (ref "H9_STLINK") (pin "11") (pinfunction "11_11") (pintype "input"))
    )
    (net (code "85") (name "unconnected-(H9_STLINK-Pad17)") (class "Default")
      (node (ref "H9_STLINK") (pin "17") (pinfunction "17_17") (pintype "input"))
    )
    (net (code "86") (name "unconnected-(H9_STLINK-Pad19)") (class "Default")
      (node (ref "H9_STLINK") (pin "19") (pinfunction "19_19") (pintype "input"))
    )
    (net (code "87") (name "unconnected-(H10-Pad4)") (class "Default")
      (node (ref "H10") (pin "4") (pinfunction "4_4") (pintype "unspecified+no_connect"))
    )
    (net (code "88") (name "unconnected-(H10-Pad5)") (class "Default")
      (node (ref "H10") (pin "5") (pinfunction "5_5") (pintype "unspecified+no_connect"))
    )
    (net (code "89") (name "unconnected-(H11-Pad4)") (class "Default")
      (node (ref "H11") (pin "4") (pinfunction "4_4") (pintype "input"))
    )
    (net (code "90") (name "unconnected-(U3-PA0-Pad34)") (class "Default")
      (node (ref "U3") (pin "34") (pinfunction "PA0_34") (pintype "unspecified"))
    )
    (net (code "91") (name "unconnected-(U3-PA1-Pad35)") (class "Default")
      (node (ref "U3") (pin "35") (pinfunction "PA1_35") (pintype "unspecified"))
    )
    (net (code "92") (name "unconnected-(U3-PA4-Pad40)") (class "Default")
      (node (ref "U3") (pin "40") (pinfunction "PA4_40") (pintype "unspecified"))
    )
    (net (code "93") (name "unconnected-(U3-PA5-Pad41)") (class "Default")
      (node (ref "U3") (pin "41") (pinfunction "PA5_41") (pintype "unspecified"))
    )
    (net (code "94") (name "unconnected-(U3-PA6-Pad42)") (class "Default")
      (node (ref "U3") (pin "42") (pinfunction "PA6_42") (pintype "unspecified"))
    )
    (net (code "95") (name "unconnected-(U3-PA7-Pad43)") (class "Default")
      (node (ref "U3") (pin "43") (pinfunction "PA7_43") (pintype "unspecified"))
    )
    (net (code "96") (name "unconnected-(U3-PA11-Pad103)") (class "Default")
      (node (ref "U3") (pin "103") (pinfunction "PA11_103") (pintype "unspecified"))
    )
    (net (code "97") (name "unconnected-(U3-PA12-Pad104)") (class "Default")
      (node (ref "U3") (pin "104") (pinfunction "PA12_104") (pintype "unspecified"))
    )
    (net (code "98") (name "unconnected-(U3-PB0-Pad46)") (class "Default")
      (node (ref "U3") (pin "46") (pinfunction "PB0_46") (pintype "unspecified"))
    )
    (net (code "99") (name "unconnected-(U3-PB1-Pad47)") (class "Default")
      (node (ref "U3") (pin "47") (pinfunction "PB1_47") (pintype "unspecified"))
    )
    (net (code "100") (name "unconnected-(U3-PB2-Pad48)") (class "Default")
      (node (ref "U3") (pin "48") (pinfunction "PB2_48") (pintype "unspecified"))
    )
    (net (code "101") (name "unconnected-(U3-PB5-Pad135)") (class "Default")
      (node (ref "U3") (pin "135") (pinfunction "PB5_135") (pintype "unspecified"))
    )
    (net (code "102") (name "unconnected-(U3-PB6-Pad136)") (class "Default")
      (node (ref "U3") (pin "136") (pinfunction "PB6_136") (pintype "unspecified"))
    )
    (net (code "103") (name "unconnected-(U3-PB7-Pad137)") (class "Default")
      (node (ref "U3") (pin "137") (pinfunction "PB7_137") (pintype "unspecified"))
    )
    (net (code "104") (name "unconnected-(U3-PB8-Pad139)") (class "Default")
      (node (ref "U3") (pin "139") (pinfunction "PB8_139") (pintype "unspecified"))
    )
    (net (code "105") (name "unconnected-(U3-PB9-Pad140)") (class "Default")
      (node (ref "U3") (pin "140") (pinfunction "PB9_140") (pintype "unspecified"))
    )
    (net (code "106") (name "unconnected-(U3-PB10-Pad69)") (class "Default")
      (node (ref "U3") (pin "69") (pinfunction "PB10_69") (pintype "unspecified"))
    )
    (net (code "107") (name "unconnected-(U3-PB11-Pad70)") (class "Default")
      (node (ref "U3") (pin "70") (pinfunction "PB11_70") (pintype "unspecified"))
    )
    (net (code "108") (name "unconnected-(U3-PB12-Pad73)") (class "Default")
      (node (ref "U3") (pin "73") (pinfunction "PB12_73") (pintype "unspecified"))
    )
    (net (code "109") (name "unconnected-(U3-PB13-Pad74)") (class "Default")
      (node (ref "U3") (pin "74") (pinfunction "PB13_74") (pintype "unspecified"))
    )
    (net (code "110") (name "unconnected-(U3-PB14-Pad75)") (class "Default")
      (node (ref "U3") (pin "75") (pinfunction "PB14_75") (pintype "unspecified"))
    )
    (net (code "111") (name "unconnected-(U3-PB15-Pad76)") (class "Default")
      (node (ref "U3") (pin "76") (pinfunction "PB15_76") (pintype "unspecified"))
    )
    (net (code "112") (name "unconnected-(U3-PC0-Pad26)") (class "Default")
      (node (ref "U3") (pin "26") (pinfunction "PC0_26") (pintype "unspecified"))
    )
    (net (code "113") (name "unconnected-(U3-PC1-Pad27)") (class "Default")
      (node (ref "U3") (pin "27") (pinfunction "PC1_27") (pintype "unspecified"))
    )
    (net (code "114") (name "unconnected-(U3-PC2-Pad28)") (class "Default")
      (node (ref "U3") (pin "28") (pinfunction "PC2_28") (pintype "unspecified"))
    )
    (net (code "115") (name "unconnected-(U3-PC3-Pad29)") (class "Default")
      (node (ref "U3") (pin "29") (pinfunction "PC3_29") (pintype "unspecified"))
    )
    (net (code "116") (name "unconnected-(U3-PC4-Pad44)") (class "Default")
      (node (ref "U3") (pin "44") (pinfunction "PC4_44") (pintype "unspecified"))
    )
    (net (code "117") (name "unconnected-(U3-PC5-Pad45)") (class "Default")
      (node (ref "U3") (pin "45") (pinfunction "PC5_45") (pintype "unspecified"))
    )
    (net (code "118") (name "unconnected-(U3-PC6-Pad96)") (class "Default")
      (node (ref "U3") (pin "96") (pinfunction "PC6_96") (pintype "unspecified"))
    )
    (net (code "119") (name "unconnected-(U3-PC7-Pad97)") (class "Default")
      (node (ref "U3") (pin "97") (pinfunction "PC7_97") (pintype "unspecified"))
    )
    (net (code "120") (name "unconnected-(U3-PC8-Pad98)") (class "Default")
      (node (ref "U3") (pin "98") (pinfunction "PC8_98") (pintype "unspecified"))
    )
    (net (code "121") (name "unconnected-(U3-PC10-Pad111)") (class "Default")
      (node (ref "U3") (pin "111") (pinfunction "PC10_111") (pintype "unspecified"))
    )
    (net (code "122") (name "unconnected-(U3-PC11-Pad112)") (class "Default")
      (node (ref "U3") (pin "112") (pinfunction "PC11_112") (pintype "unspecified"))
    )
    (net (code "123") (name "unconnected-(U3-PC12-Pad113)") (class "Default")
      (node (ref "U3") (pin "113") (pinfunction "PC12_113") (pintype "unspecified"))
    )
    (net (code "124") (name "unconnected-(U3-PC13-Pad7)") (class "Default")
      (node (ref "U3") (pin "7") (pinfunction "PC13_7") (pintype "unspecified"))
    )
    (net (code "125") (name "unconnected-(U3-PC14-Pad8)") (class "Default")
      (node (ref "U3") (pin "8") (pinfunction "PC14_8") (pintype "unspecified"))
    )
    (net (code "126") (name "unconnected-(U3-PC15-Pad9)") (class "Default")
      (node (ref "U3") (pin "9") (pinfunction "PC15_9") (pintype "unspecified"))
    )
    (net (code "127") (name "unconnected-(U3-PD2-Pad116)") (class "Default")
      (node (ref "U3") (pin "116") (pinfunction "PD2_116") (pintype "unspecified"))
    )
    (net (code "128") (name "unconnected-(U3-PD6-Pad122)") (class "Default")
      (node (ref "U3") (pin "122") (pinfunction "PD6_122") (pintype "unspecified"))
    )
    (net (code "129") (name "unconnected-(U3-PD8-Pad77)") (class "Default")
      (node (ref "U3") (pin "77") (pinfunction "PD8_77") (pintype "unspecified"))
    )
    (net (code "130") (name "unconnected-(U3-PD9-Pad78)") (class "Default")
      (node (ref "U3") (pin "78") (pinfunction "PD9_78") (pintype "unspecified"))
    )
    (net (code "131") (name "unconnected-(U3-PD10-Pad79)") (class "Default")
      (node (ref "U3") (pin "79") (pinfunction "PD10_79") (pintype "unspecified"))
    )
    (net (code "132") (name "unconnected-(U3-PD11-Pad80)") (class "Default")
      (node (ref "U3") (pin "80") (pinfunction "PD11_80") (pintype "unspecified"))
    )
    (net (code "133") (name "unconnected-(U3-PD12-Pad81)") (class "Default")
      (node (ref "U3") (pin "81") (pinfunction "PD12_81") (pintype "unspecified"))
    )
    (net (code "134") (name "unconnected-(U3-PD13-Pad82)") (class "Default")
      (node (ref "U3") (pin "82") (pinfunction "PD13_82") (pintype "unspecified"))
    )
    (net (code "135") (name "unconnected-(U3-PE0-Pad141)") (class "Default")
      (node (ref "U3") (pin "141") (pinfunction "PE0_141") (pintype "unspecified"))
    )
    (net (code "136") (name "unconnected-(U3-PE1-Pad142)") (class "Default")
      (node (ref "U3") (pin "142") (pinfunction "PE1_142") (pintype "unspecified"))
    )
    (net (code "137") (name "unconnected-(U3-PE2-Pad1)") (class "Default")
      (node (ref "U3") (pin "1") (pinfunction "PE2_1") (pintype "unspecified"))
    )
    (net (code "138") (name "unconnected-(U3-PE3-Pad2)") (class "Default")
      (node (ref "U3") (pin "2") (pinfunction "PE3_2") (pintype "unspecified"))
    )
    (net (code "139") (name "unconnected-(U3-PE4-Pad3)") (class "Default")
      (node (ref "U3") (pin "3") (pinfunction "PE4_3") (pintype "unspecified"))
    )
    (net (code "140") (name "unconnected-(U3-PE5-Pad4)") (class "Default")
      (node (ref "U3") (pin "4") (pinfunction "PE5_4") (pintype "unspecified"))
    )
    (net (code "141") (name "unconnected-(U3-PE6-Pad5)") (class "Default")
      (node (ref "U3") (pin "5") (pinfunction "PE6_5") (pintype "unspecified"))
    )
    (net (code "142") (name "unconnected-(U3-PE11-Pad64)") (class "Default")
      (node (ref "U3") (pin "64") (pinfunction "PE11_64") (pintype "unspecified"))
    )
    (net (code "143") (name "unconnected-(U3-PE12-Pad65)") (class "Default")
      (node (ref "U3") (pin "65") (pinfunction "PE12_65") (pintype "unspecified"))
    )
    (net (code "144") (name "unconnected-(U3-PE13-Pad66)") (class "Default")
      (node (ref "U3") (pin "66") (pinfunction "PE13_66") (pintype "unspecified"))
    )
    (net (code "145") (name "unconnected-(U3-PE14-Pad67)") (class "Default")
      (node (ref "U3") (pin "67") (pinfunction "PE14_67") (pintype "unspecified"))
    )
    (net (code "146") (name "unconnected-(U3-PE15-Pad68)") (class "Default")
      (node (ref "U3") (pin "68") (pinfunction "PE15_68") (pintype "unspecified"))
    )
    (net (code "147") (name "unconnected-(U3-PF6-Pad18)") (class "Default")
      (node (ref "U3") (pin "18") (pinfunction "PF6_18") (pintype "unspecified"))
    )
    (net (code "148") (name "unconnected-(U3-PF7-Pad19)") (class "Default")
      (node (ref "U3") (pin "19") (pinfunction "PF7_19") (pintype "unspecified"))
    )
    (net (code "149") (name "unconnected-(U3-PF8-Pad20)") (class "Default")
      (node (ref "U3") (pin "20") (pinfunction "PF8_20") (pintype "unspecified"))
    )
    (net (code "150") (name "unconnected-(U3-PF9-Pad21)") (class "Default")
      (node (ref "U3") (pin "21") (pinfunction "PF9_21") (pintype "unspecified"))
    )
    (net (code "151") (name "unconnected-(U3-PF10-Pad22)") (class "Default")
      (node (ref "U3") (pin "22") (pinfunction "PF10_22") (pintype "unspecified"))
    )
    (net (code "152") (name "unconnected-(U3-PF11-Pad49)") (class "Default")
      (node (ref "U3") (pin "49") (pinfunction "PF11_49") (pintype "unspecified"))
    )
    (net (code "153") (name "unconnected-(U3-PG3-Pad88)") (class "Default")
      (node (ref "U3") (pin "88") (pinfunction "PG3_88") (pintype "unspecified"))
    )
    (net (code "154") (name "unconnected-(U3-PG4-Pad89)") (class "Default")
      (node (ref "U3") (pin "89") (pinfunction "PG4_89") (pintype "unspecified"))
    )
    (net (code "155") (name "unconnected-(U3-PG5-Pad90)") (class "Default")
      (node (ref "U3") (pin "90") (pinfunction "PG5_90") (pintype "unspecified"))
    )
    (net (code "156") (name "unconnected-(U3-PG6-Pad91)") (class "Default")
      (node (ref "U3") (pin "91") (pinfunction "PG6_91") (pintype "unspecified"))
    )
    (net (code "157") (name "unconnected-(U3-PG7-Pad92)") (class "Default")
      (node (ref "U3") (pin "92") (pinfunction "PG7_92") (pintype "unspecified"))
    )
    (net (code "158") (name "unconnected-(U3-PG8-Pad93)") (class "Default")
      (node (ref "U3") (pin "93") (pinfunction "PG8_93") (pintype "unspecified"))
    )
    (net (code "159") (name "unconnected-(U3-PG11-Pad126)") (class "Default")
      (node (ref "U3") (pin "126") (pinfunction "PG11_126") (pintype "unspecified"))
    )
    (net (code "160") (name "unconnected-(U3-PG13-Pad128)") (class "Default")
      (node (ref "U3") (pin "128") (pinfunction "PG13_128") (pintype "unspecified"))
    )
    (net (code "161") (name "unconnected-(U3-PG14-Pad129)") (class "Default")
      (node (ref "U3") (pin "129") (pinfunction "PG14_129") (pintype "unspecified"))
    )
    (net (code "162") (name "unconnected-(U3-PG15-Pad132)") (class "Default")
      (node (ref "U3") (pin "132") (pinfunction "PG15_132") (pintype "unspecified"))
    )
    (net (code "163") (name "unconnected-(U6-NC-Pad129)") (class "Default")
      (node (ref "U6") (pin "129") (pinfunction "NC_129") (pintype "unspecified"))
    )
    (net (code "164") (name "unconnected-(U6-PB3A-Pad38)") (class "Default")
      (node (ref "U6") (pin "38") (pinfunction "PB3A_38") (pintype "unspecified"))
    )
    (net (code "165") (name "unconnected-(U6-PB3B-Pad39)") (class "Default")
      (node (ref "U6") (pin "39") (pinfunction "PB3B_39") (pintype "unspecified"))
    )
    (net (code "166") (name "unconnected-(U6-PB4A-Pad40)") (class "Default")
      (node (ref "U6") (pin "40") (pinfunction "PB4A_40") (pintype "unspecified"))
    )
    (net (code "167") (name "unconnected-(U6-PB4B-Pad41)") (class "Default")
      (node (ref "U6") (pin "41") (pinfunction "PB4B_41") (pintype "unspecified"))
    )
    (net (code "168") (name "unconnected-(U6-PB7A-Pad42)") (class "Default")
      (node (ref "U6") (pin "42") (pinfunction "PB7A_42") (pintype "unspecified"))
    )
    (net (code "169") (name "unconnected-(U6-PB7B-Pad43)") (class "Default")
      (node (ref "U6") (pin "43") (pinfunction "PB7B_43") (pintype "unspecified"))
    )
    (net (code "170") (name "unconnected-(U6-PB9A-Pad44)") (class "Default")
      (node (ref "U6") (pin "44") (pinfunction "PB9A_44") (pintype "unspecified"))
    )
    (net (code "171") (name "unconnected-(U6-PB9B-Pad45)") (class "Default")
      (node (ref "U6") (pin "45") (pinfunction "PB9B_45") (pintype "unspecified"))
    )
    (net (code "172") (name "unconnected-(U6-PB10A-Pad47)") (class "Default")
      (node (ref "U6") (pin "47") (pinfunction "PB10A_47") (pintype "unspecified"))
    )
    (net (code "173") (name "unconnected-(U6-PB10B-Pad48)") (class "Default")
      (node (ref "U6") (pin "48") (pinfunction "PB10B_48") (pintype "unspecified"))
    )
    (net (code "174") (name "unconnected-(U6-PB13A-Pad49)") (class "Default")
      (node (ref "U6") (pin "49") (pinfunction "PB13A_49") (pintype "unspecified"))
    )
    (net (code "175") (name "unconnected-(U6-PB13B-Pad50)") (class "Default")
      (node (ref "U6") (pin "50") (pinfunction "PB13B_50") (pintype "unspecified"))
    )
    (net (code "176") (name "unconnected-(U6-PB24B-Pad62)") (class "Default")
      (node (ref "U6") (pin "62") (pinfunction "PB24B_62") (pintype "unspecified"))
    )
    (net (code "177") (name "unconnected-(U6-PB24D-Pad63)") (class "Default")
      (node (ref "U6") (pin "63") (pinfunction "PB24D_63") (pintype "unspecified"))
    )
    (net (code "178") (name "unconnected-(U6-PB27A-Pad65)") (class "Default")
      (node (ref "U6") (pin "65") (pinfunction "PB27A_65") (pintype "unspecified"))
    )
    (net (code "179") (name "unconnected-(U6-PB27B-Pad67)") (class "Default")
      (node (ref "U6") (pin "67") (pinfunction "PB27B_67") (pintype "unspecified"))
    )
    (net (code "180") (name "unconnected-(U6-PB29A-Pad68)") (class "Default")
      (node (ref "U6") (pin "68") (pinfunction "PB29A_68") (pintype "unspecified"))
    )
    (net (code "181") (name "unconnected-(U6-PB29B-Pad69)") (class "Default")
      (node (ref "U6") (pin "69") (pinfunction "PB29B_69") (pintype "unspecified"))
    )
    (net (code "182") (name "unconnected-(U6-PB30A-Pad70)") (class "Default")
      (node (ref "U6") (pin "70") (pinfunction "PB30A_70") (pintype "unspecified"))
    )
    (net (code "183") (name "unconnected-(U6-PB30B-Pad71)") (class "Default")
      (node (ref "U6") (pin "71") (pinfunction "PB30B_71") (pintype "unspecified"))
    )
    (net (code "184") (name "unconnected-(U6-PL3A-Pad1)") (class "Default")
      (node (ref "U6") (pin "1") (pinfunction "PL3A_1") (pintype "unspecified"))
    )
    (net (code "185") (name "unconnected-(U6-PL3B-Pad2)") (class "Default")
      (node (ref "U6") (pin "2") (pinfunction "PL3B_2") (pintype "unspecified"))
    )
    (net (code "186") (name "unconnected-(U6-PL4A-Pad3)") (class "Default")
      (node (ref "U6") (pin "3") (pinfunction "PL4A_3") (pintype "unspecified"))
    )
    (net (code "187") (name "unconnected-(U6-PL4B-Pad4)") (class "Default")
      (node (ref "U6") (pin "4") (pinfunction "PL4B_4") (pintype "unspecified"))
    )
    (net (code "188") (name "unconnected-(U6-PL6A-Pad5)") (class "Default")
      (node (ref "U6") (pin "5") (pinfunction "PL6A_5") (pintype "unspecified"))
    )
    (net (code "189") (name "unconnected-(U6-PL6B-Pad6)") (class "Default")
      (node (ref "U6") (pin "6") (pinfunction "PL6B_6") (pintype "unspecified"))
    )
    (net (code "190") (name "unconnected-(U6-PL7A-Pad9)") (class "Default")
      (node (ref "U6") (pin "9") (pinfunction "PL7A_9") (pintype "unspecified"))
    )
    (net (code "191") (name "unconnected-(U6-PL7B-Pad10)") (class "Default")
      (node (ref "U6") (pin "10") (pinfunction "PL7B_10") (pintype "unspecified"))
    )
    (net (code "192") (name "unconnected-(U6-PL8A-Pad11)") (class "Default")
      (node (ref "U6") (pin "11") (pinfunction "PL8A_11") (pintype "unspecified"))
    )
    (net (code "193") (name "unconnected-(U6-PL8B-Pad12)") (class "Default")
      (node (ref "U6") (pin "12") (pinfunction "PL8B_12") (pintype "unspecified"))
    )
    (net (code "194") (name "unconnected-(U6-PL9A-Pad13)") (class "Default")
      (node (ref "U6") (pin "13") (pinfunction "PL9A_13") (pintype "unspecified"))
    )
    (net (code "195") (name "unconnected-(U6-PL9B-Pad14)") (class "Default")
      (node (ref "U6") (pin "14") (pinfunction "PL9B_14") (pintype "unspecified"))
    )
    (net (code "196") (name "unconnected-(U6-PL10A-Pad15)") (class "Default")
      (node (ref "U6") (pin "15") (pinfunction "PL10A_15") (pintype "unspecified"))
    )
    (net (code "197") (name "unconnected-(U6-PL10B-Pad17)") (class "Default")
      (node (ref "U6") (pin "17") (pinfunction "PL10B_17") (pintype "unspecified"))
    )
    (net (code "198") (name "unconnected-(U6-PL14B-Pad24)") (class "Default")
      (node (ref "U6") (pin "24") (pinfunction "PL14B_24") (pintype "unspecified"))
    )
    (net (code "199") (name "unconnected-(U6-PL16A-Pad25)") (class "Default")
      (node (ref "U6") (pin "25") (pinfunction "PL16A_25") (pintype "unspecified"))
    )
    (net (code "200") (name "unconnected-(U6-PL16B-Pad26)") (class "Default")
      (node (ref "U6") (pin "26") (pinfunction "PL16B_26") (pintype "unspecified"))
    )
    (net (code "201") (name "unconnected-(U6-PL17A-Pad27)") (class "Default")
      (node (ref "U6") (pin "27") (pinfunction "PL17A_27") (pintype "unspecified"))
    )
    (net (code "202") (name "unconnected-(U6-PL17B-Pad28)") (class "Default")
      (node (ref "U6") (pin "28") (pinfunction "PL17B_28") (pintype "unspecified"))
    )
    (net (code "203") (name "unconnected-(U6-PL18D-Pad31)") (class "Default")
      (node (ref "U6") (pin "31") (pinfunction "PL18D_31") (pintype "unspecified"))
    )
    (net (code "204") (name "unconnected-(U6-PL19A-Pad32)") (class "Default")
      (node (ref "U6") (pin "32") (pinfunction "PL19A_32") (pintype "unspecified"))
    )
    (net (code "205") (name "unconnected-(U6-PL19B-Pad33)") (class "Default")
      (node (ref "U6") (pin "33") (pinfunction "PL19B_33") (pintype "unspecified"))
    )
    (net (code "206") (name "unconnected-(U6-PL20A-Pad34)") (class "Default")
      (node (ref "U6") (pin "34") (pinfunction "PL20A_34") (pintype "unspecified"))
    )
    (net (code "207") (name "unconnected-(U6-PL20B-Pad35)") (class "Default")
      (node (ref "U6") (pin "35") (pinfunction "PL20B_35") (pintype "unspecified"))
    )
    (net (code "208") (name "unconnected-(U6-PR10B-Pad91)") (class "Default")
      (node (ref "U6") (pin "91") (pinfunction "PR10B_91") (pintype "unspecified"))
    )
    (net (code "209") (name "unconnected-(U6-PR10C-Pad89)") (class "Default")
      (node (ref "U6") (pin "89") (pinfunction "PR10C_89") (pintype "unspecified"))
    )
    (net (code "210") (name "unconnected-(U6-PR10D-Pad87)") (class "Default")
      (node (ref "U6") (pin "87") (pinfunction "PR10D_87") (pintype "unspecified"))
    )
    (net (code "211") (name "unconnected-(U6-PR13B-Pad85)") (class "Default")
      (node (ref "U6") (pin "85") (pinfunction "PR13B_85") (pintype "unspecified"))
    )
    (net (code "212") (name "unconnected-(U6-PR19A-Pad74)") (class "Default")
      (node (ref "U6") (pin "74") (pinfunction "PR19A_74") (pintype "unspecified"))
    )
    (net (code "213") (name "unconnected-(U6-PR19B-Pad73)") (class "Default")
      (node (ref "U6") (pin "73") (pinfunction "PR19B_73") (pintype "unspecified"))
    )
    (net (code "214") (name "unconnected-(U6-PT9A-Pad143)") (class "Default")
      (node (ref "U6") (pin "143") (pinfunction "PT9A_143") (pintype "unspecified"))
    )
    (net (code "215") (name "unconnected-(U6-PT9B-Pad142)") (class "Default")
      (node (ref "U6") (pin "142") (pinfunction "PT9B_142") (pintype "unspecified"))
    )
    (net (code "216") (name "unconnected-(U6-PT10A-Pad141)") (class "Default")
      (node (ref "U6") (pin "141") (pinfunction "PT10A_141") (pintype "unspecified"))
    )
    (net (code "217") (name "unconnected-(U6-PT10B-Pad140)") (class "Default")
      (node (ref "U6") (pin "140") (pinfunction "PT10B_140") (pintype "unspecified"))
    )
    (net (code "218") (name "unconnected-(U6-PT11A-Pad139)") (class "Default")
      (node (ref "U6") (pin "139") (pinfunction "PT11A_139") (pintype "unspecified"))
    )
    (net (code "219") (name "unconnected-(U6-PT11B-Pad138)") (class "Default")
      (node (ref "U6") (pin "138") (pinfunction "PT11B_138") (pintype "unspecified"))
    )
    (net (code "220") (name "unconnected-(U6-PT14A-Pad133)") (class "Default")
      (node (ref "U6") (pin "133") (pinfunction "PT14A_133") (pintype "unspecified"))
    )
    (net (code "221") (name "unconnected-(U6-PT14B-Pad132)") (class "Default")
      (node (ref "U6") (pin "132") (pinfunction "PT14B_132") (pintype "unspecified"))
    )
    (net (code "222") (name "unconnected-(U6-PT20C-Pad126)") (class "Default")
      (node (ref "U6") (pin "126") (pinfunction "PT20C_126") (pintype "unspecified"))
    )
    (net (code "223") (name "unconnected-(U6-PT20D-Pad125)") (class "Default")
      (node (ref "U6") (pin "125") (pinfunction "PT20D_125") (pintype "unspecified"))
    )
    (net (code "224") (name "unconnected-(U6-PT21A-Pad122)") (class "Default")
      (node (ref "U6") (pin "122") (pinfunction "PT21A_122") (pintype "unspecified"))
    )
    (net (code "225") (name "unconnected-(U6-PT21B-Pad121)") (class "Default")
      (node (ref "U6") (pin "121") (pinfunction "PT21B_121") (pintype "unspecified"))
    )
    (net (code "226") (name "unconnected-(U6-PT23C-Pad120)") (class "Default")
      (node (ref "U6") (pin "120") (pinfunction "PT23C_120") (pintype "unspecified"))
    )
    (net (code "227") (name "unconnected-(U6-PT23D-Pad119)") (class "Default")
      (node (ref "U6") (pin "119") (pinfunction "PT23D_119") (pintype "unspecified"))
    )
    (net (code "228") (name "unconnected-(U6-PT24A-Pad117)") (class "Default")
      (node (ref "U6") (pin "117") (pinfunction "PT24A_117") (pintype "unspecified"))
    )
    (net (code "229") (name "unconnected-(U6-PT24B-Pad115)") (class "Default")
      (node (ref "U6") (pin "115") (pinfunction "PT24B_115") (pintype "unspecified"))
    )
    (net (code "230") (name "unconnected-(U6-PT25A-Pad114)") (class "Default")
      (node (ref "U6") (pin "114") (pinfunction "PT25A_114") (pintype "unspecified"))
    )
    (net (code "231") (name "unconnected-(U6-PT25B-Pad113)") (class "Default")
      (node (ref "U6") (pin "113") (pinfunction "PT25B_113") (pintype "unspecified"))
    )
    (net (code "232") (name "unconnected-(U6-PT27A-Pad112)") (class "Default")
      (node (ref "U6") (pin "112") (pinfunction "PT27A_112") (pintype "unspecified"))
    )
    (net (code "233") (name "unconnected-(U6-PT27B-Pad111)") (class "Default")
      (node (ref "U6") (pin "111") (pinfunction "PT27B_111") (pintype "unspecified"))
    )
    (net (code "234") (name "unconnected-(U6-PT28C-Pad110)") (class "Default")
      (node (ref "U6") (pin "110") (pinfunction "PT28C_110") (pintype "unspecified"))
    )
    (net (code "235") (name "unconnected-(U6-PT28D-Pad109)") (class "Default")
      (node (ref "U6") (pin "109") (pinfunction "PT28D_109") (pintype "unspecified"))
    )
    (net (code "236") (name "unconnected-(U7-RTS#-Pad4)") (class "Default")
      (node (ref "U7") (pin "4") (pinfunction "RTS#_4") (pintype "unspecified"))
    )
    (net (code "237") (name "unconnected-(U18-Pad2)") (class "Default")
      (node (ref "U18") (pin "2") (pinfunction "2_2") (pintype "unspecified"))
    )
  )
)
